# usb_esp32_cp2104.net
KiCad netlist of a schematic drawn in Altium Designer
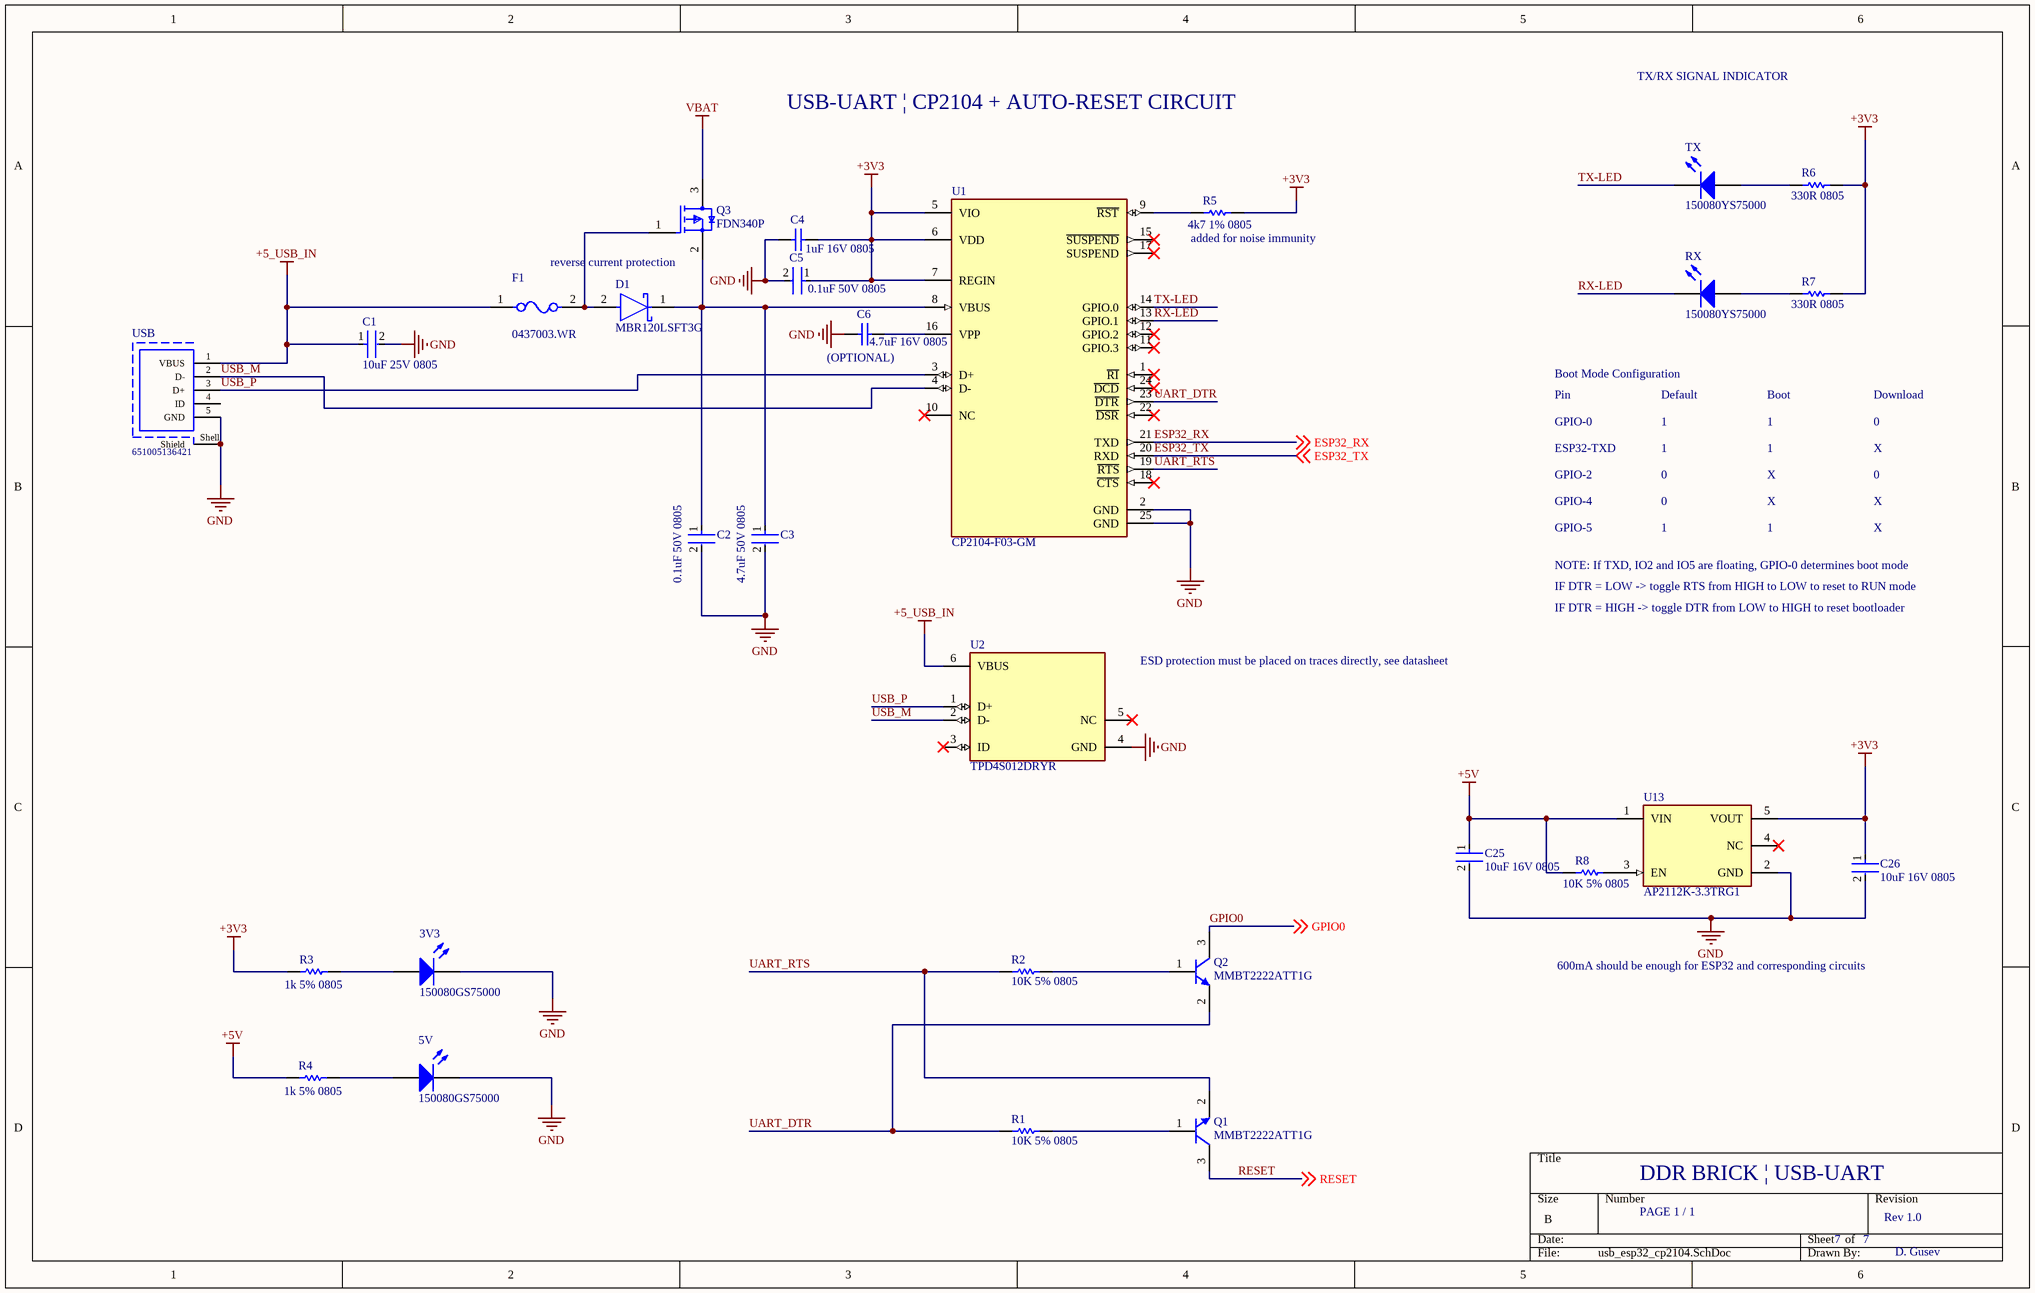
[diagram p0: usb_esp32_cp2104.SchDoc]

(export (version "E")
  (design (tool "Eeschema 10.0.6"))
  (components
    (comp (ref "3V3")
      (value "150080GS75000")
      (footprint "0805_A")
      (description "SMD mono-color Chip LED, WL-SMCW, Green")
      (fields (field (name "MANUFACTURER") "Wuerth Elektronik"))
      (libsource (lib "Altium Content Vault") (part "WE-LED_K1A2-2"))
    )
    (comp (ref "5V")
      (value "150080GS75000")
      (footprint "0805_A")
      (description "SMD mono-color Chip LED, WL-SMCW, Green")
      (fields (field (name "MANUFACTURER") "Wuerth Elektronik"))
      (libsource (lib "Altium Content Vault") (part "WE-LED_K1A2-2"))
    )
    (comp (ref "C1")
      (value "10uF 25V 0805")
      (footprint "FP-GRM21B-0_15-IPC_C")
      (description "Chip Multilayer Ceramic Capacitors for General Purpose, 0805, 10uF, X5R, 15%, 10%, 25V")
      (fields (field (name "VOLTAGE") "25V") (field (name "TOLERANCE") "10%"))
      (libsource (lib "Altium Content Vault") (part "b4654b650e69147ec39a6b967a45e02"))
    )
    (comp (ref "C2")
      (value "0.1uF 50V 0805")
      (footprint "FP-C0805C-DN-MFG")
      (description "CAP CER 0.1UF 50V X7R 0805")
      (fields
        (field (name "MANUFACTURER PART NUMBER") "C0805C104K5RACTU")
        (field (name "MANUFACTURER") "KEMET")
      )
      (libsource (lib "Altium Content Vault") (part "b4654b650e69147ec39a6b967a45e02"))
    )
    (comp (ref "C3")
      (value "4.7uF 50V 0805")
      (footprint "FP-C2012-125-MFG")
      (description "CAP CER 4.7UF 50V X5R 0805")
      (fields
        (field (name "TOLERANCE") "10%")
        (field (name "MANUFACTURER PART NUMBER") "C2012X5R1H475K125AB")
      )
      (libsource (lib "Altium Content Vault") (part "11868f565c42a9108669ba33697ecf6"))
    )
    (comp (ref "C4")
      (value "1uF 16V 0805")
      (footprint "CAPC2013X145X50LL20T25")
      (fields (field (name "MANUFACTURER") "Kemet") (field (name "PART NUMBER") "C0805C105K4PACTU"))
      (libsource (lib "Altium Content Vault") (part "CAP"))
    )
    (comp (ref "C5")
      (value "0.1uF 50V 0805")
      (footprint "FP-C0805C-DN-MFG")
      (description "CAP CER 0.1UF 50V X7R 0805")
      (fields
        (field (name "MANUFACTURER PART NUMBER") "C0805C104K5RACTU")
        (field (name "MANUFACTURER") "KEMET")
      )
      (libsource (lib "Altium Content Vault") (part "b4654b650e69147ec39a6b967a45e02"))
    )
    (comp (ref "C6")
      (value "4.7uF 16V 0805")
      (footprint "CAPC2013X140X50LL20T25")
      (fields (field (name "PART NUMBER") "C0805C475K4PACTU") (field (name "MANUFACTURER") "Kemet"))
      (libsource (lib "Altium Content Vault") (part "CAP"))
    )
    (comp (ref "C25")
      (value "10uF 16V 0805")
      (footprint "FP-GRM21B-0_1-IPC_C")
      (description "Chip Multilayer Ceramic Capacitors for General Purpose, 0805, 10uF, X5R, 15%, 10%, 16V")
      (fields (field (name "TOLERANCE") "10%") (field (name "VOLTAGE") "16V"))
      (libsource (lib "Altium Content Vault") (part "b4654b650e69147ec39a6b967a45e02"))
    )
    (comp (ref "C26")
      (value "10uF 16V 0805")
      (footprint "FP-GRM21B-0_1-IPC_C")
      (description "Chip Multilayer Ceramic Capacitors for General Purpose, 0805, 10uF, X5R, 15%, 10%, 16V")
      (fields (field (name "TOLERANCE") "10%") (field (name "VOLTAGE") "16V"))
      (libsource (lib "Altium Content Vault") (part "b4654b650e69147ec39a6b967a45e02"))
    )
    (comp (ref "D1")
      (value "MBR120LSFT3G")
      (footprint "FP-498-MFG")
      (description "DIODE SCHOTTKY 20V 1A SOD123L")
      (libsource (lib "Altium Content Vault") (part "1d6ec82d83fb6aee721767c19dac4b9"))
    )
    (comp (ref "F1")
      (value "0437003.WR")
      (footprint "FP-437-MFG")
      (description "FUSE BRD MNT 3A 32VAC 35VDC 1206")
      (fields
        (field (name "OCTOPART") "https://octopart.com/0437003.wr-littelfuse-8600121")
        (field (name "MANUFACTURER") "Littelfuse Inc")
      )
      (libsource (lib "Altium Content Vault") (part "5bcf9b9f640e542cf0359d10258e979"))
    )
    (comp (ref "Q1")
      (value "MMBT2222ATT1G")
      (footprint "ONSC-SC-75-3-463-01_V")
      (description "General Purpose Transistor, NPN Silicon, 3-Pin SC-75, Pb-Free, Tape and Reel")
      (fields (field (name "MANUFACTURER") "On Semiconductor"))
      (libsource (lib "Altium Content Vault") (part "ONSC-NPN-B1E2C3-3"))
    )
    (comp (ref "Q2")
      (value "MMBT2222ATT1G")
      (footprint "ONSC-SC-75-3-463-01_V")
      (description "General Purpose Transistor, NPN Silicon, 3-Pin SC-75, Pb-Free, Tape and Reel")
      (fields (field (name "MANUFACTURER") "On Semiconductor"))
      (libsource (lib "Altium Content Vault") (part "ONSC-NPN-B1E2C3-3"))
    )
    (comp (ref "Q3")
      (value "FDN340P")
      (footprint "FP-527AG-MFG")
      (description "MOSFET P-CH 20V 2A SSOT3")
      (libsource (lib "Altium Content Vault") (part "d23f43cc42f60b967b7caccf14518fd"))
    )
    (comp (ref "R1")
      (value "10K 5% 0805")
      (footprint "RESC2013X60X40ML20T25")
      (fields (field (name "PART NUMBER") "ERA6AEB123V") (field (name "MANUFACTURER") "Panasonic"))
      (libsource (lib "Altium Content Vault") (part "RES"))
    )
    (comp (ref "R2")
      (value "10K 5% 0805")
      (footprint "RESC2013X60X40ML20T25")
      (fields (field (name "PART NUMBER") "ERA6AEB123V") (field (name "MANUFACTURER") "Panasonic"))
      (libsource (lib "Altium Content Vault") (part "RES"))
    )
    (comp (ref "R3")
      (value "1k 5% 0805")
      (footprint "RESC2013X60X35ML10T20")
      (description "Chip Resistor, 1 KOhm, +/- 1%, 125 mW, -55 to 155 degC, 0805 (2012 Metric), RoHS, Tape and Reel")
      (fields (field (name "TOLERANCE") "1%") (field (name "MANUFACTURER") "Yageo"))
      (libsource (lib "Altium Content Vault") (part "RES-2"))
    )
    (comp (ref "R4")
      (value "1k 5% 0805")
      (footprint "RESC2013X60X35ML10T20")
      (description "Chip Resistor, 1 KOhm, +/- 1%, 125 mW, -55 to 155 degC, 0805 (2012 Metric), RoHS, Tape and Reel")
      (fields (field (name "TOLERANCE") "1%") (field (name "MANUFACTURER") "Yageo"))
      (libsource (lib "Altium Content Vault") (part "RES-2"))
    )
    (comp (ref "R5")
      (value "4k7 1% 0805")
      (footprint "YAGO-RC0805_M")
      (fields
        (field (name "TOLERANCE") "+/- 1%")
        (field (name "PARTNUMBER") "RC0805FR-074K7L")
        (field (name "POWER") "0.125 W")
      )
      (libsource (lib "Altium Content Vault") (part "YAGO-RES-2"))
    )
    (comp (ref "R6")
      (value "330R 0805")
      (footprint "RESC2013X60X35LL10T20")
      (description "Chip Resistor, 330 Ohm, +/- 1%, 125 mW, -55 to 155 degC, 0805 (2012 Metric), RoHS, Tape and Reel")
      (fields (field (name "MANUFACTURER") "Yageo") (field (name "TOLERANCE") "1%"))
      (libsource (lib "Altium Content Vault") (part "RES-2"))
    )
    (comp (ref "R7")
      (value "330R 0805")
      (footprint "RESC2013X60X35LL10T20")
      (description "Chip Resistor, 330 Ohm, +/- 1%, 125 mW, -55 to 155 degC, 0805 (2012 Metric), RoHS, Tape and Reel")
      (fields (field (name "MANUFACTURER") "Yageo") (field (name "TOLERANCE") "1%"))
      (libsource (lib "Altium Content Vault") (part "RES-2"))
    )
    (comp (ref "R8")
      (value "10K 5% 0805")
      (footprint "RESC2013X60X40ML20T25")
      (fields (field (name "PART NUMBER") "ERA6AEB123V") (field (name "MANUFACTURER") "Panasonic"))
      (libsource (lib "Altium Content Vault") (part "RES"))
    )
    (comp (ref "RX")
      (value "150080YS75000")
      (footprint "0805_A")
      (description "SMD mono-color Chip LED, WL-SMCW, Yellow")
      (fields (field (name "MANUFACTURER") "Wuerth Elektronik"))
      (libsource (lib "Altium Content Vault") (part "WE-LED_K1A2-2"))
    )
    (comp (ref "TX")
      (value "150080YS75000")
      (footprint "0805_A")
      (description "SMD mono-color Chip LED, WL-SMCW, Yellow")
      (fields (field (name "MANUFACTURER") "Wuerth Elektronik"))
      (libsource (lib "Altium Content Vault") (part "WE-LED_K1A2-2"))
    )
    (comp (ref "U1")
      (value "CP2104-F03-GM")
      (footprint "FP-CP2104-F03-GM-MFG")
      (description "IC SGL USB-TO-UART BRIDGE 24QFN")
      (libsource (lib "Altium Content Vault") (part "36aa9e967c7f1036f799a443da3d357"))
    )
    (comp (ref "U2")
      (value "TPD4S012DRYR")
      (footprint "FP-DRY0006A-MFG")
      (description "TVS DIODE 5.5V 6SON")
      (libsource (lib "Altium Content Vault") (part "0f51f1bc734c3fed0021f16fcfaf2e1"))
    )
    (comp (ref "U13")
      (value "AP2112K-3.3TRG1")
      (footprint "FP-SOT25-IPC_A")
      (description "IC REG LINEAR 3.3V 600MA SOT25")
      (libsource (lib "Altium Content Vault") (part "c8ab751aee5229183125ab046a11caa"))
    )
    (comp (ref "USB")
      (value "651005136421")
      (footprint "651005136421")
      (description "Mini USB 2.0 Type B Receptacle WR-COM, Vertical, THT")
      (fields (field (name "MANUFACTURER") "Wurth Elektronik") (field (name "PUBLISHER") "WurthElektronik"))
      (libsource (lib "Altium Content Vault") (part "WE-USB-5-1SHLD"))
    )
  )
  (nets
    (net (code "1") (name "+3V3") (class "Default")
      (node (ref "C26") (pin "1") (pinfunction "1_1") (pintype "passive"))
      (node (ref "C4") (pin "2") (pinfunction "2_2") (pintype "passive"))
      (node (ref "C5") (pin "1") (pinfunction "1_1") (pintype "passive"))
      (node (ref "R3") (pin "1") (pinfunction "1_1") (pintype "passive"))
      (node (ref "R5") (pin "2") (pinfunction "2_2") (pintype "passive"))
      (node (ref "R6") (pin "2") (pinfunction "2_2") (pintype "passive"))
      (node (ref "R7") (pin "2") (pinfunction "2_2") (pintype "passive"))
      (node (ref "U1") (pin "5") (pinfunction "VIO_5") (pintype "power_in"))
      (node (ref "U1") (pin "6") (pinfunction "VDD_6") (pintype "power_in"))
      (node (ref "U1") (pin "7") (pinfunction "REGIN_7") (pintype "power_in"))
      (node (ref "U13") (pin "5") (pinfunction "VOUT_5") (pintype "power_in"))
    )
    (net (code "2") (name "+5V") (class "Default")
      (node (ref "C25") (pin "1") (pinfunction "1_1") (pintype "passive"))
      (node (ref "R4") (pin "1") (pinfunction "1_1") (pintype "passive"))
      (node (ref "R8") (pin "2") (pinfunction "2_2") (pintype "passive"))
      (node (ref "U13") (pin "1") (pinfunction "VIN_1") (pintype "power_in"))
    )
    (net (code "3") (name "+5_USB_IN") (class "Default")
      (node (ref "C1") (pin "1") (pinfunction "1_1") (pintype "passive"))
      (node (ref "F1") (pin "1") (pinfunction "1_1") (pintype "passive"))
      (node (ref "U2") (pin "6") (pinfunction "VBUS_6") (pintype "passive"))
      (node (ref "USB") (pin "1") (pinfunction "VBUS_1") (pintype "passive"))
    )
    (net (code "4") (name "/RX-LED") (class "Default")
      (node (ref "RX") (pin "1") (pinfunction "K_1") (pintype "passive"))
      (node (ref "U1") (pin "13") (pinfunction "GPIO.1_13") (pintype "bidirectional"))
    )
    (net (code "5") (name "/TX-LED") (class "Default")
      (node (ref "TX") (pin "1") (pinfunction "K_1") (pintype "passive"))
      (node (ref "U1") (pin "14") (pinfunction "GPIO.0_14") (pintype "bidirectional"))
    )
    (net (code "6") (name "/UART_DTR") (class "Default")
      (node (ref "Q2") (pin "2") (pinfunction "E_2") (pintype "passive"))
      (node (ref "R1") (pin "2") (pinfunction "2_2") (pintype "passive"))
      (node (ref "U1") (pin "23") (pinfunction "~{DTR}_23") (pintype "output"))
    )
    (net (code "7") (name "/UART_RTS") (class "Default")
      (node (ref "Q1") (pin "2") (pinfunction "E_2") (pintype "passive"))
      (node (ref "R2") (pin "2") (pinfunction "2_2") (pintype "passive"))
      (node (ref "U1") (pin "19") (pinfunction "~{RTS}_19") (pintype "output"))
    )
    (net (code "8") (name "/USB_M") (class "Default")
      (node (ref "U1") (pin "4") (pinfunction "D-_4") (pintype "bidirectional"))
      (node (ref "U2") (pin "2") (pinfunction "D-_2") (pintype "bidirectional"))
      (node (ref "USB") (pin "2") (pinfunction "D-_2") (pintype "passive"))
    )
    (net (code "9") (name "/USB_P") (class "Default")
      (node (ref "U1") (pin "3") (pinfunction "D+_3") (pintype "bidirectional"))
      (node (ref "U2") (pin "1") (pinfunction "D+_1") (pintype "bidirectional"))
      (node (ref "USB") (pin "3") (pinfunction "D+_3") (pintype "passive"))
    )
    (net (code "10") (name "ESP32_RX") (class "Default")
      (node (ref "U1") (pin "21") (pinfunction "TXD_21") (pintype "output"))
    )
    (net (code "11") (name "ESP32_TX") (class "Default")
      (node (ref "U1") (pin "20") (pinfunction "RXD_20") (pintype "input"))
    )
    (net (code "12") (name "GND") (class "Default")
      (node (ref "3V3") (pin "1") (pinfunction "K_1") (pintype "passive"))
      (node (ref "5V") (pin "1") (pinfunction "K_1") (pintype "passive"))
      (node (ref "C1") (pin "2") (pinfunction "2_2") (pintype "passive"))
      (node (ref "C2") (pin "2") (pinfunction "2_2") (pintype "passive"))
      (node (ref "C25") (pin "2") (pinfunction "2_2") (pintype "passive"))
      (node (ref "C26") (pin "2") (pinfunction "2_2") (pintype "passive"))
      (node (ref "C3") (pin "2") (pinfunction "2_2") (pintype "passive"))
      (node (ref "C4") (pin "1") (pinfunction "1_1") (pintype "passive"))
      (node (ref "C5") (pin "2") (pinfunction "2_2") (pintype "passive"))
      (node (ref "C6") (pin "2") (pinfunction "2_2") (pintype "passive"))
      (node (ref "U1") (pin "2") (pinfunction "GND_2") (pintype "power_in"))
      (node (ref "U1") (pin "25") (pinfunction "GND_25") (pintype "power_in"))
      (node (ref "U13") (pin "2") (pinfunction "GND_2") (pintype "power_in"))
      (node (ref "U2") (pin "4") (pinfunction "GND_4") (pintype "power_in"))
      (node (ref "USB") (pin "5") (pinfunction "GND_5") (pintype "passive"))
      (node (ref "USB") (pin "Shell") (pinfunction "Shield_Shell") (pintype "passive"))
    )
    (net (code "13") (name "GPIO0") (class "Default")
      (node (ref "Q2") (pin "3") (pinfunction "C_3") (pintype "passive"))
    )
    (net (code "14") (name "Net-(3V3-A)") (class "Default")
      (node (ref "3V3") (pin "2") (pinfunction "A_2") (pintype "passive"))
      (node (ref "R3") (pin "2") (pinfunction "2_2") (pintype "passive"))
    )
    (net (code "15") (name "Net-(5V-A)") (class "Default")
      (node (ref "5V") (pin "2") (pinfunction "A_2") (pintype "passive"))
      (node (ref "R4") (pin "2") (pinfunction "2_2") (pintype "passive"))
    )
    (net (code "16") (name "Net-(D1-A)") (class "Default")
      (node (ref "D1") (pin "2") (pinfunction "A_2") (pintype "passive"))
      (node (ref "F1") (pin "2") (pinfunction "2_2") (pintype "passive"))
      (node (ref "Q3") (pin "1") (pinfunction "G_1") (pintype "passive"))
    )
    (net (code "17") (name "Net-(D1-C)") (class "Default")
      (node (ref "C2") (pin "1") (pinfunction "1_1") (pintype "passive"))
      (node (ref "C3") (pin "1") (pinfunction "1_1") (pintype "passive"))
      (node (ref "D1") (pin "1") (pinfunction "C_1") (pintype "passive"))
      (node (ref "Q3") (pin "2") (pinfunction "S_2") (pintype "passive"))
      (node (ref "U1") (pin "8") (pinfunction "VBUS_8") (pintype "input"))
    )
    (net (code "18") (name "Net-(Q1-B)") (class "Default")
      (node (ref "Q1") (pin "1") (pinfunction "B_1") (pintype "passive"))
      (node (ref "R1") (pin "1") (pinfunction "1_1") (pintype "passive"))
    )
    (net (code "19") (name "Net-(Q2-B)") (class "Default")
      (node (ref "Q2") (pin "1") (pinfunction "B_1") (pintype "passive"))
      (node (ref "R2") (pin "1") (pinfunction "1_1") (pintype "passive"))
    )
    (net (code "20") (name "Net-(RX-A)") (class "Default")
      (node (ref "R7") (pin "1") (pinfunction "1_1") (pintype "passive"))
      (node (ref "RX") (pin "2") (pinfunction "A_2") (pintype "passive"))
    )
    (net (code "21") (name "Net-(TX-A)") (class "Default")
      (node (ref "R6") (pin "1") (pinfunction "1_1") (pintype "passive"))
      (node (ref "TX") (pin "2") (pinfunction "A_2") (pintype "passive"))
    )
    (net (code "22") (name "Net-(U1-VPP)") (class "Default")
      (node (ref "C6") (pin "1") (pinfunction "1_1") (pintype "passive"))
      (node (ref "U1") (pin "16") (pinfunction "VPP_16") (pintype "passive"))
    )
    (net (code "23") (name "Net-(U1-~{RST})") (class "Default")
      (node (ref "R5") (pin "1") (pinfunction "1_1") (pintype "passive"))
      (node (ref "U1") (pin "9") (pinfunction "~{RST}_9") (pintype "bidirectional"))
    )
    (net (code "24") (name "Net-(U13-EN)") (class "Default")
      (node (ref "R8") (pin "1") (pinfunction "1_1") (pintype "passive"))
      (node (ref "U13") (pin "3") (pinfunction "EN_3") (pintype "input"))
    )
    (net (code "25") (name "RESET") (class "Default")
      (node (ref "Q1") (pin "3") (pinfunction "C_3") (pintype "passive"))
    )
    (net (code "26") (name "VBAT") (class "Default")
      (node (ref "Q3") (pin "3") (pinfunction "D_3") (pintype "passive"))
    )
    (net (code "27") (name "unconnected-(U1-GPIO.2-Pad12)") (class "Default")
      (node (ref "U1") (pin "12") (pinfunction "GPIO.2_12") (pintype "bidirectional+no_connect"))
    )
    (net (code "28") (name "unconnected-(U1-GPIO.3-Pad11)") (class "Default")
      (node (ref "U1") (pin "11") (pinfunction "GPIO.3_11") (pintype "bidirectional+no_connect"))
    )
    (net (code "29") (name "unconnected-(U1-NC-Pad10)") (class "Default")
      (node (ref "U1") (pin "10") (pinfunction "NC_10") (pintype "passive+no_connect"))
    )
    (net (code "30") (name "unconnected-(U1-SUSPEND-Pad17)") (class "Default")
      (node (ref "U1") (pin "17") (pinfunction "SUSPEND_17") (pintype "output+no_connect"))
    )
    (net (code "31") (name "unconnected-(U1-~{CTS}-Pad18)") (class "Default")
      (node (ref "U1") (pin "18") (pinfunction "~{CTS}_18") (pintype "input+no_connect"))
    )
    (net (code "32") (name "unconnected-(U1-~{DCD}-Pad24)") (class "Default")
      (node (ref "U1") (pin "24") (pinfunction "~{DCD}_24") (pintype "input+no_connect"))
    )
    (net (code "33") (name "unconnected-(U1-~{DSR}-Pad22)") (class "Default")
      (node (ref "U1") (pin "22") (pinfunction "~{DSR}_22") (pintype "input+no_connect"))
    )
    (net (code "34") (name "unconnected-(U1-~{RI}-Pad1)") (class "Default")
      (node (ref "U1") (pin "1") (pinfunction "~{RI}_1") (pintype "input+no_connect"))
    )
    (net (code "35") (name "unconnected-(U1-~{SUSPEND}-Pad15)") (class "Default")
      (node (ref "U1") (pin "15") (pinfunction "~{SUSPEND}_15") (pintype "output+no_connect"))
    )
    (net (code "36") (name "unconnected-(U2-ID-Pad3)") (class "Default")
      (node (ref "U2") (pin "3") (pinfunction "ID_3") (pintype "bidirectional+no_connect"))
    )
    (net (code "37") (name "unconnected-(U2-NC-Pad5)") (class "Default")
      (node (ref "U2") (pin "5") (pinfunction "NC_5") (pintype "passive+no_connect"))
    )
    (net (code "38") (name "unconnected-(U13-NC-Pad4)") (class "Default")
      (node (ref "U13") (pin "4") (pinfunction "NC_4") (pintype "passive+no_connect"))
    )
    (net (code "39") (name "unconnected-(USB-ID-Pad4)") (class "Default")
      (node (ref "USB") (pin "4") (pinfunction "ID_4") (pintype "passive"))
    )
  )
)
